# RF315Mhz.net
KiCad netlist of a schematic drawn in Altium Designer
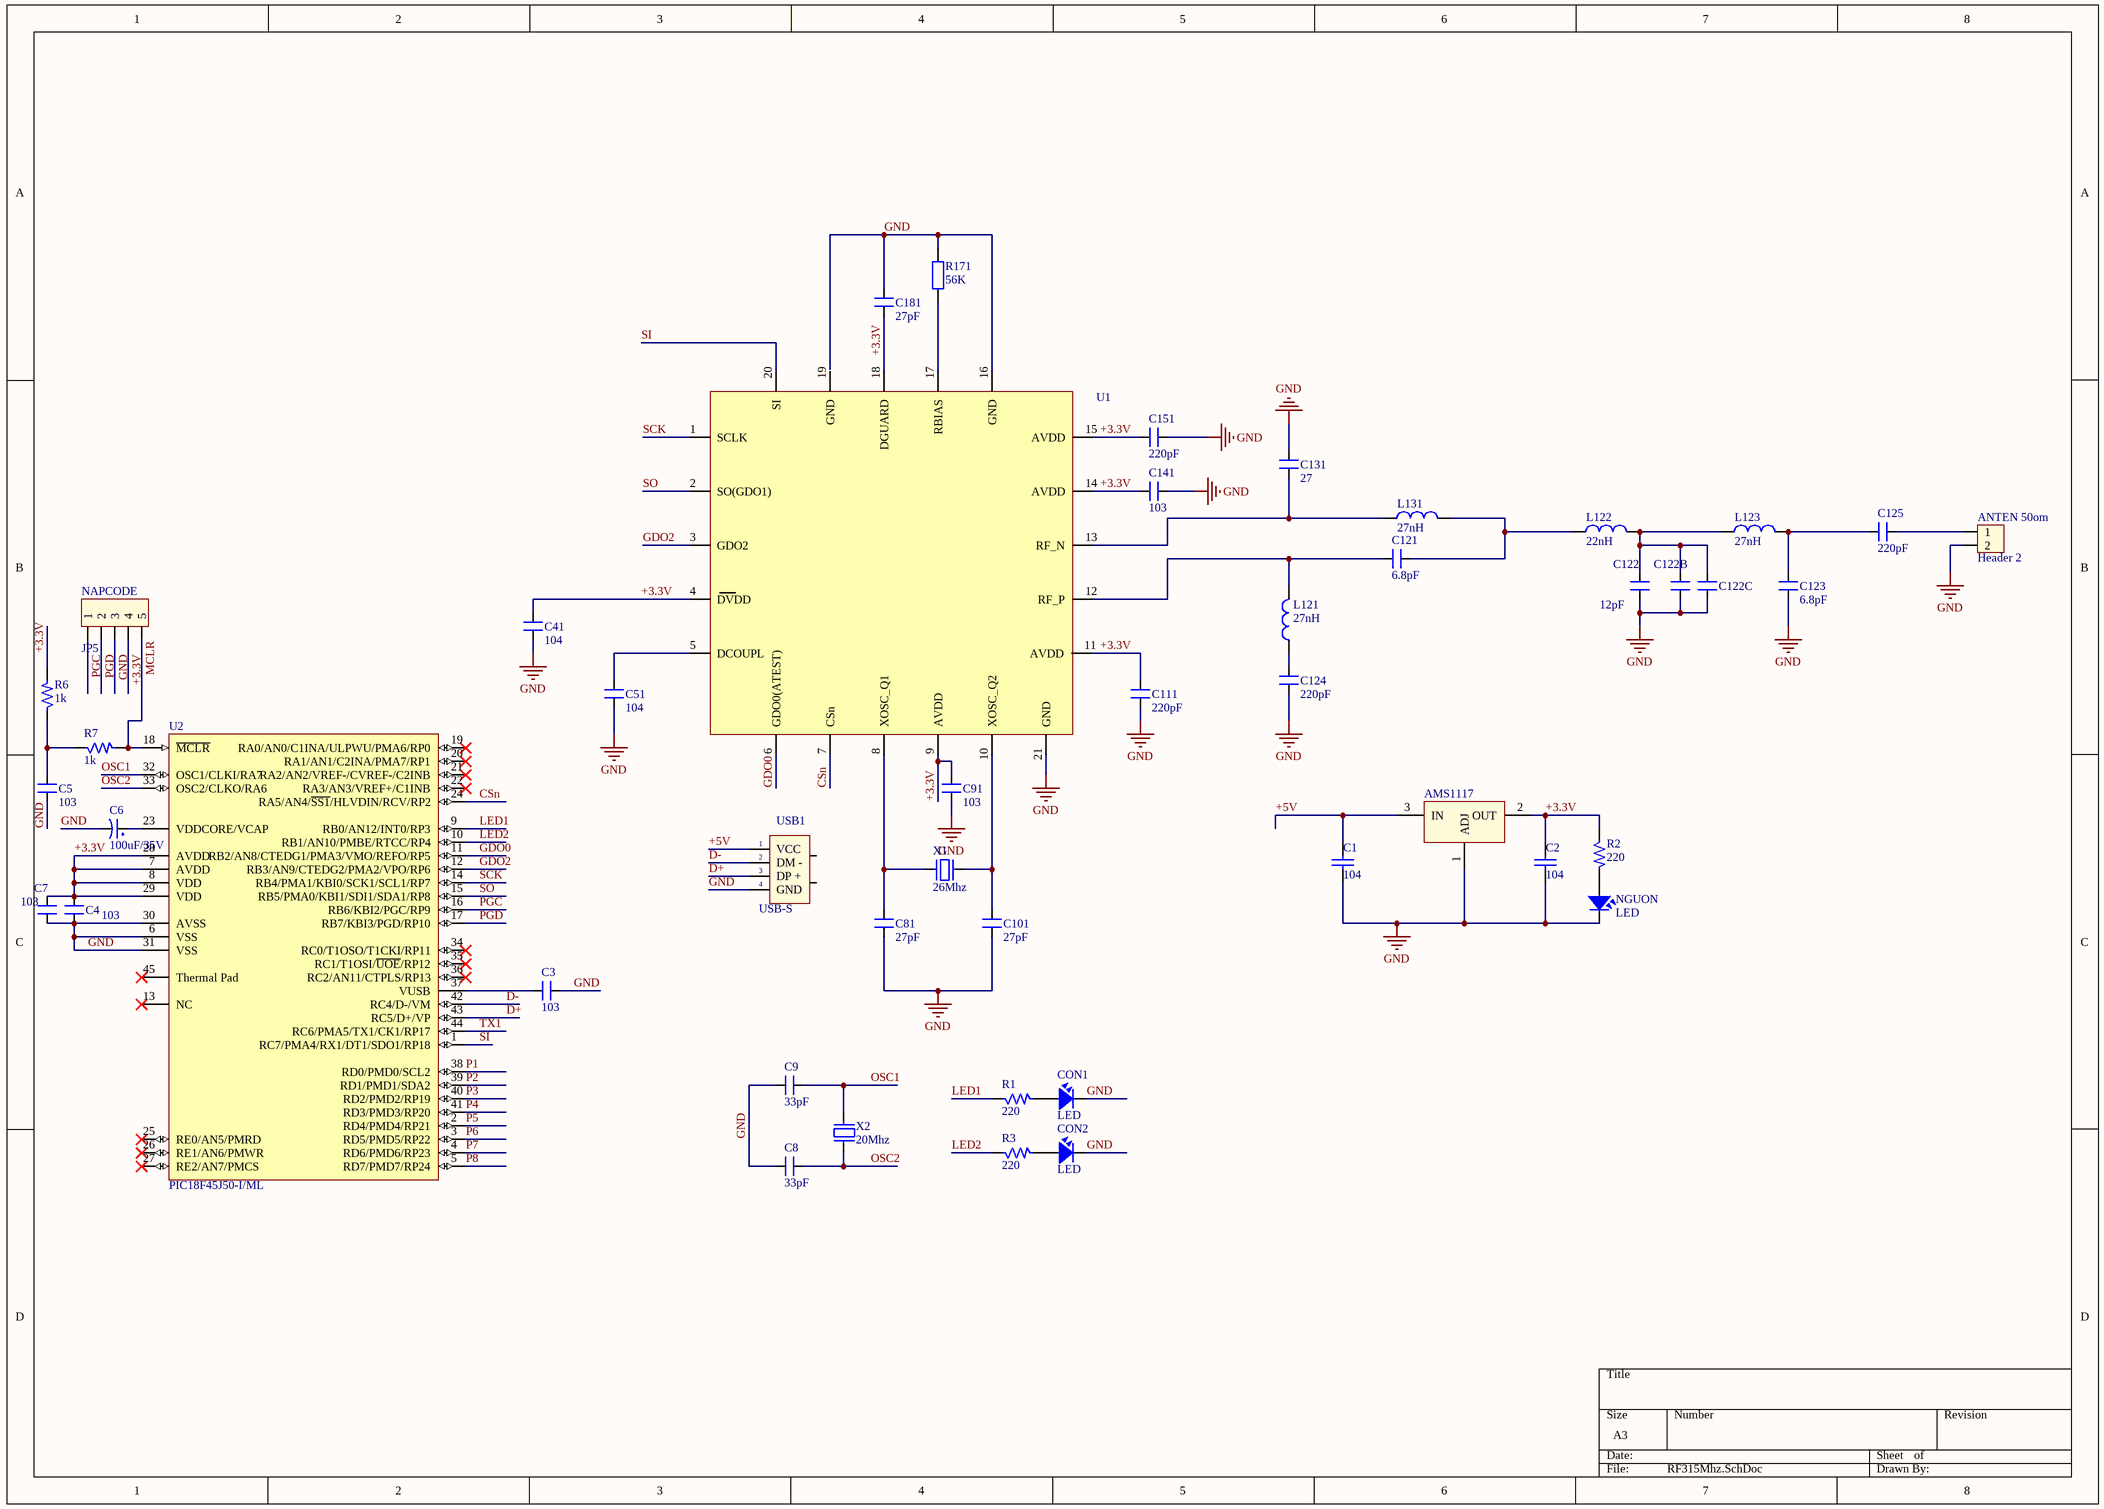
[diagram p0: RF315Mhz.SchDoc]

(export (version "E")
  (design (tool "Eeschema 10.0.6"))
  (components
    (comp (ref "AMS1117")
      (value "LM317")
      (footprint "SOT223-4N")
      (description "Adj Voltage +1.2 -> +37V")
      (libsource (lib "syhaunguyen") (part "LM317"))
    )
    (comp (ref "ANTEN 50om")
      (value "Header 2")
      (footprint "MCX5.08-H5")
      (description "Header 2 (Green)")
      (libsource (lib "syhaunguyen") (part "Hed2"))
    )
    (comp (ref "C1")
      (value "104")
      (footprint "0603ESDA")
      (description "Capacitor")
      (fields (field (name "PUBLISHER") "Altium Limited"))
      (libsource (lib "Miscellaneous Devices") (part "Cap"))
    )
    (comp (ref "C2")
      (value "104")
      (footprint "0603ESDA")
      (description "Capacitor")
      (fields (field (name "PUBLISHER") "Altium Limited"))
      (libsource (lib "Miscellaneous Devices") (part "Cap"))
    )
    (comp (ref "C3")
      (value "103")
      (footprint "SM-0805")
      (description "Cap SMD")
      (libsource (lib "syhaunguyen") (part "CM"))
    )
    (comp (ref "C4")
      (value "103")
      (footprint "SM-0805")
      (description "Cap SMD")
      (libsource (lib "syhaunguyen") (part "CM"))
    )
    (comp (ref "C5")
      (value "103")
      (footprint "SM-0805")
      (description "Cap SMD")
      (libsource (lib "syhaunguyen") (part "CM"))
    )
    (comp (ref "C6")
      (value "100uF/35V")
      (footprint "CP1/2.5_SM")
      (description "Cap 100uF/35V - 470uF/16V")
      (libsource (lib "syhaunguyen") (part "CP3"))
    )
    (comp (ref "C7")
      (value "103")
      (footprint "SM-0805")
      (description "Cap SMD")
      (libsource (lib "syhaunguyen") (part "CM"))
    )
    (comp (ref "C8")
      (value "33pF")
      (footprint "SM-0805")
      (description "Cremic For Xtal 1pF => 100pF")
      (libsource (lib "syhaunguyen") (part "CN0"))
    )
    (comp (ref "C9")
      (value "33pF")
      (footprint "SM-0805")
      (description "Cremic For Xtal 1pF => 100pF")
      (libsource (lib "syhaunguyen") (part "CN0"))
    )
    (comp (ref "C41")
      (value "104")
      (footprint "0603ESDA")
      (description "Cap SMD")
      (libsource (lib "syhaunguyen") (part "CM"))
    )
    (comp (ref "C51")
      (value "104")
      (footprint "0603ESDA")
      (description "Cap SMD")
      (libsource (lib "syhaunguyen") (part "CM"))
    )
    (comp (ref "C81")
      (value "27pF")
      (footprint "0603ESDA")
      (description "Cap SMD")
      (libsource (lib "syhaunguyen") (part "CM"))
    )
    (comp (ref "C91")
      (value "103")
      (footprint "0603ESDA")
      (description "Cap SMD")
      (libsource (lib "syhaunguyen") (part "CM"))
    )
    (comp (ref "C101")
      (value "27pF")
      (footprint "0603ESDA")
      (description "Cap SMD")
      (libsource (lib "syhaunguyen") (part "CM"))
    )
    (comp (ref "C111")
      (value "220pF")
      (footprint "0603ESDA")
      (description "Cap SMD")
      (libsource (lib "syhaunguyen") (part "CM"))
    )
    (comp (ref "C121")
      (value "6.8pF")
      (footprint "0603ESDA")
      (description "Cap SMD")
      (libsource (lib "syhaunguyen") (part "CM"))
    )
    (comp (ref "C122")
      (value "12pF")
      (footprint "0603ESDA")
      (description "Cap SMD")
      (libsource (lib "syhaunguyen") (part "CM"))
    )
    (comp (ref "C122B")
      (value "12pF")
      (footprint "0603ESDA")
      (description "Cap SMD")
      (libsource (lib "syhaunguyen") (part "CM"))
    )
    (comp (ref "C122C")
      (value "12pF")
      (footprint "0603ESDA")
      (description "Cap SMD")
      (libsource (lib "syhaunguyen") (part "CM"))
    )
    (comp (ref "C123")
      (value "6.8pF")
      (footprint "0603ESDA")
      (description "Cap SMD")
      (libsource (lib "syhaunguyen") (part "CM"))
    )
    (comp (ref "C124")
      (value "220pF")
      (footprint "0603ESDA")
      (description "Cap SMD")
      (libsource (lib "syhaunguyen") (part "CM"))
    )
    (comp (ref "C125")
      (value "220pF")
      (footprint "0603ESDA")
      (description "Cap SMD")
      (libsource (lib "syhaunguyen") (part "CM"))
    )
    (comp (ref "C131")
      (value "27")
      (footprint "0603ESDA")
      (description "Cap SMD")
      (libsource (lib "syhaunguyen") (part "CM"))
    )
    (comp (ref "C141")
      (value "103")
      (footprint "0603ESDA")
      (description "Cap SMD")
      (libsource (lib "syhaunguyen") (part "CM"))
    )
    (comp (ref "C151")
      (value "220pF")
      (footprint "0603ESDA")
      (description "Cap SMD")
      (libsource (lib "syhaunguyen") (part "CM"))
    )
    (comp (ref "C181")
      (value "27pF")
      (footprint "0603ESDA")
      (description "Cap SMD")
      (libsource (lib "syhaunguyen") (part "CM"))
    )
    (comp (ref "CON1")
      (value "LED")
      (footprint "LED3mm")
      (description "LED Single colour Green and Red")
      (libsource (lib "syhaunguyen") (part "LED"))
    )
    (comp (ref "CON2")
      (value "LED")
      (footprint "LED3mm")
      (description "LED Single colour Green and Red")
      (libsource (lib "syhaunguyen") (part "LED"))
    )
    (comp (ref "L121")
      (value "27nH")
      (footprint "SM-0805")
      (description "Inductor")
      (libsource (lib "syhaunguyen") (part "L1"))
    )
    (comp (ref "L122")
      (value "22nH")
      (footprint "SM-0805")
      (description "Inductor")
      (libsource (lib "syhaunguyen") (part "L1"))
    )
    (comp (ref "L123")
      (value "27nH")
      (footprint "SM-0805")
      (description "Inductor")
      (libsource (lib "syhaunguyen") (part "L1"))
    )
    (comp (ref "L131")
      (value "27nH")
      (footprint "SM-0805")
      (description "Inductor")
      (libsource (lib "syhaunguyen") (part "L1"))
    )
    (comp (ref "NAPCODE")
      (value "JP5")
      (footprint "CON5")
      (description "Connector 5")
      (libsource (lib "syhaunguyen") (part "Con5"))
    )
    (comp (ref "NGUON")
      (value "LED")
      (footprint "LED0805")
      (description "LED Single colour Green and Red")
      (libsource (lib "syhaunguyen") (part "LED"))
    )
    (comp (ref "R1")
      (value "220")
      (footprint "SM-0805")
      (description "Resistor 1/4W")
      (libsource (lib "syhaunguyen") (part "R"))
    )
    (comp (ref "R2")
      (value "220")
      (footprint "SM-0805")
      (description "Resistor 1/4W")
      (libsource (lib "syhaunguyen") (part "R"))
    )
    (comp (ref "R3")
      (value "220")
      (footprint "SM-0805")
      (description "Resistor 1/4W")
      (libsource (lib "syhaunguyen") (part "R"))
    )
    (comp (ref "R6")
      (value "1k")
      (footprint "SM-0805")
      (description "Resistor 1/4W")
      (libsource (lib "syhaunguyen") (part "R"))
    )
    (comp (ref "R7")
      (value "1k")
      (footprint "SM-0805")
      (description "Resistor 1/4W")
      (libsource (lib "syhaunguyen") (part "R"))
    )
    (comp (ref "R171")
      (value "56K")
      (footprint "SM-0805")
      (description "Resistor SMD")
      (libsource (lib "syhaunguyen") (part "RM"))
    )
    (comp (ref "U1")
      (value "CC1101")
      (footprint "QFN-20Pin")
      (description "Transceiver 315Mhz")
      (libsource (lib "syhaunguyen") (part "CC1101"))
    )
    (comp (ref "U2")
      (value "PIC18F45J50-I/ML")
      (footprint "PIC18F45J50SMD")
      (fields (field (name "PUBLISHER") "Altium Limited"))
      (libsource (lib "Microchip Microcontroller 8-Bit PIC18") (part "PIC18F45J50-I/ML"))
    )
    (comp (ref "USB1")
      (value "USB-S")
      (footprint "USB-A")
      (description "USB connector")
      (libsource (lib "syhaunguyen") (part "USB_S"))
    )
    (comp (ref "X1")
      (value "26Mhz")
      (footprint "XT2")
      (description "Crystal For all Crystal 2pin.")
      (libsource (lib "syhaunguyen") (part "XT2"))
    )
    (comp (ref "X2")
      (value "20Mhz")
      (footprint "XT2")
      (description "Crystal For all Crystal 2pin.")
      (libsource (lib "syhaunguyen") (part "XT2"))
    )
  )
  (nets
    (net (code "1") (name "/+3.3V") (class "Default")
      (node (ref "AMS1117") (pin "2") (pinfunction "OUT_2") (pintype "passive"))
      (node (ref "C111") (pin "2") (pinfunction "2_2") (pintype "passive"))
      (node (ref "C141") (pin "2") (pinfunction "2_2") (pintype "passive"))
      (node (ref "C151") (pin "1") (pinfunction "1_1") (pintype "passive"))
      (node (ref "C181") (pin "1") (pinfunction "1_1") (pintype "passive"))
      (node (ref "C2") (pin "2") (pinfunction "2_2") (pintype "passive"))
      (node (ref "C4") (pin "1") (pinfunction "1_1") (pintype "passive"))
      (node (ref "C41") (pin "2") (pinfunction "2_2") (pintype "passive"))
      (node (ref "C7") (pin "2") (pinfunction "2_2") (pintype "passive"))
      (node (ref "C91") (pin "2") (pinfunction "2_2") (pintype "passive"))
      (node (ref "NAPCODE") (pin "4") (pinfunction "4_4") (pintype "passive"))
      (node (ref "R2") (pin "1") (pinfunction "1_1") (pintype "passive"))
      (node (ref "R6") (pin "2") (pinfunction "2_2") (pintype "passive"))
      (node (ref "U1") (pin "11") (pinfunction "AVDD_11") (pintype "passive"))
      (node (ref "U1") (pin "14") (pinfunction "AVDD_14") (pintype "passive"))
      (node (ref "U1") (pin "15") (pinfunction "AVDD_15") (pintype "passive"))
      (node (ref "U1") (pin "18") (pinfunction "DGUARD_18") (pintype "passive"))
      (node (ref "U1") (pin "4") (pinfunction "DVDD_4") (pintype "passive"))
      (node (ref "U1") (pin "9") (pinfunction "AVDD_9") (pintype "passive"))
      (node (ref "U2") (pin "28") (pinfunction "AVDD_28") (pintype "power_in"))
      (node (ref "U2") (pin "29") (pinfunction "VDD_29") (pintype "power_in"))
      (node (ref "U2") (pin "7") (pinfunction "AVDD_7") (pintype "power_in"))
      (node (ref "U2") (pin "8") (pinfunction "VDD_8") (pintype "power_in"))
    )
    (net (code "2") (name "/+5V") (class "Default")
      (node (ref "AMS1117") (pin "3") (pinfunction "IN_3") (pintype "passive"))
      (node (ref "C1") (pin "2") (pinfunction "2_2") (pintype "passive"))
      (node (ref "USB1") (pin "1") (pinfunction "VCC_1") (pintype "passive"))
    )
    (net (code "3") (name "/CSn") (class "Default")
      (node (ref "U1") (pin "7") (pinfunction "CSn_7") (pintype "passive"))
      (node (ref "U2") (pin "24") (pinfunction "RA5/AN4/~{SS1}/HLVDIN/RCV/RP2_24") (pintype "bidirectional"))
    )
    (net (code "4") (name "/D+") (class "Default")
      (node (ref "U2") (pin "43") (pinfunction "RC5/D+/VP_43") (pintype "bidirectional"))
      (node (ref "USB1") (pin "3") (pinfunction "DP_+_3") (pintype "passive"))
    )
    (net (code "5") (name "/D-") (class "Default")
      (node (ref "U2") (pin "42") (pinfunction "RC4/D-/VM_42") (pintype "bidirectional"))
      (node (ref "USB1") (pin "2") (pinfunction "DM_-_2") (pintype "passive"))
    )
    (net (code "6") (name "/GDO0") (class "Default")
      (node (ref "U1") (pin "6") (pinfunction "GDO0(ATEST)_6") (pintype "passive"))
      (node (ref "U2") (pin "11") (pinfunction "RB2/AN8/CTEDG1/PMA3/VMO/REFO/RP5_11") (pintype "bidirectional"))
    )
    (net (code "7") (name "/GDO2") (class "Default")
      (node (ref "U1") (pin "3") (pinfunction "GDO2_3") (pintype "passive"))
      (node (ref "U2") (pin "12") (pinfunction "RB3/AN9/CTEDG2/PMA2/VPO/RP6_12") (pintype "bidirectional"))
    )
    (net (code "8") (name "/LED1") (class "Default")
      (node (ref "R1") (pin "1") (pinfunction "1_1") (pintype "passive"))
      (node (ref "U2") (pin "9") (pinfunction "RB0/AN12/INT0/RP3_9") (pintype "bidirectional"))
    )
    (net (code "9") (name "/LED2") (class "Default")
      (node (ref "R3") (pin "1") (pinfunction "1_1") (pintype "passive"))
      (node (ref "U2") (pin "10") (pinfunction "RB1/AN10/PMBE/RTCC/RP4_10") (pintype "bidirectional"))
    )
    (net (code "10") (name "/MCLR") (class "Default")
      (node (ref "NAPCODE") (pin "5") (pinfunction "5_5") (pintype "passive"))
      (node (ref "R7") (pin "2") (pinfunction "2_2") (pintype "passive"))
      (node (ref "U2") (pin "18") (pinfunction "~{MCLR}_18") (pintype "input"))
    )
    (net (code "11") (name "/OSC1") (class "Default")
      (node (ref "C9") (pin "2") (pinfunction "2_2") (pintype "passive"))
      (node (ref "U2") (pin "32") (pinfunction "OSC1/CLKI/RA7_32") (pintype "bidirectional"))
      (node (ref "X2") (pin "2") (pinfunction "2_2") (pintype "passive"))
    )
    (net (code "12") (name "/OSC2") (class "Default")
      (node (ref "C8") (pin "2") (pinfunction "2_2") (pintype "passive"))
      (node (ref "U2") (pin "33") (pinfunction "OSC2/CLKO/RA6_33") (pintype "bidirectional"))
      (node (ref "X2") (pin "1") (pinfunction "1_1") (pintype "passive"))
    )
    (net (code "13") (name "/P1") (class "Default")
      (node (ref "U2") (pin "38") (pinfunction "RD0/PMD0/SCL2_38") (pintype "bidirectional"))
    )
    (net (code "14") (name "/P2") (class "Default")
      (node (ref "U2") (pin "39") (pinfunction "RD1/PMD1/SDA2_39") (pintype "bidirectional"))
    )
    (net (code "15") (name "/P3") (class "Default")
      (node (ref "U2") (pin "40") (pinfunction "RD2/PMD2/RP19_40") (pintype "bidirectional"))
    )
    (net (code "16") (name "/P4") (class "Default")
      (node (ref "U2") (pin "41") (pinfunction "RD3/PMD3/RP20_41") (pintype "bidirectional"))
    )
    (net (code "17") (name "/P5") (class "Default")
      (node (ref "U2") (pin "2") (pinfunction "RD4/PMD4/RP21_2") (pintype "bidirectional"))
    )
    (net (code "18") (name "/P6") (class "Default")
      (node (ref "U2") (pin "3") (pinfunction "RD5/PMD5/RP22_3") (pintype "bidirectional"))
    )
    (net (code "19") (name "/P7") (class "Default")
      (node (ref "U2") (pin "4") (pinfunction "RD6/PMD6/RP23_4") (pintype "bidirectional"))
    )
    (net (code "20") (name "/P8") (class "Default")
      (node (ref "U2") (pin "5") (pinfunction "RD7/PMD7/RP24_5") (pintype "bidirectional"))
    )
    (net (code "21") (name "/PGC") (class "Default")
      (node (ref "NAPCODE") (pin "1") (pinfunction "1_1") (pintype "passive"))
      (node (ref "U2") (pin "16") (pinfunction "RB6/KBI2/PGC/RP9_16") (pintype "bidirectional"))
    )
    (net (code "22") (name "/PGD") (class "Default")
      (node (ref "NAPCODE") (pin "2") (pinfunction "2_2") (pintype "passive"))
      (node (ref "U2") (pin "17") (pinfunction "RB7/KBI3/PGD/RP10_17") (pintype "bidirectional"))
    )
    (net (code "23") (name "/SCK") (class "Default")
      (node (ref "U1") (pin "1") (pinfunction "SCLK_1") (pintype "passive"))
      (node (ref "U2") (pin "14") (pinfunction "RB4/PMA1/KBI0/SCK1/SCL1/RP7_14") (pintype "bidirectional"))
    )
    (net (code "24") (name "/SI") (class "Default")
      (node (ref "U1") (pin "20") (pinfunction "SI_20") (pintype "passive"))
      (node (ref "U2") (pin "1") (pinfunction "RC7/PMA4/RX1/DT1/SDO1/RP18_1") (pintype "bidirectional"))
    )
    (net (code "25") (name "/SO") (class "Default")
      (node (ref "U1") (pin "2") (pinfunction "SO(GDO1)_2") (pintype "passive"))
      (node (ref "U2") (pin "15") (pinfunction "RB5/PMA0/KBI1/SDI1/SDA1/RP8_15") (pintype "bidirectional"))
    )
    (net (code "26") (name "/TX1") (class "Default")
      (node (ref "U2") (pin "44") (pinfunction "RC6/PMA5/TX1/CK1/RP17_44") (pintype "bidirectional"))
    )
    (net (code "27") (name "GND") (class "Default")
      (node (ref "AMS1117") (pin "1") (pinfunction "ADJ_1") (pintype "passive"))
      (node (ref "ANTEN 50om") (pin "2") (pinfunction "2_2") (pintype "passive"))
      (node (ref "C1") (pin "1") (pinfunction "1_1") (pintype "passive"))
      (node (ref "C101") (pin "1") (pinfunction "1_1") (pintype "passive"))
      (node (ref "C111") (pin "1") (pinfunction "1_1") (pintype "passive"))
      (node (ref "C122") (pin "2") (pinfunction "2_2") (pintype "passive"))
      (node (ref "C122B") (pin "2") (pinfunction "2_2") (pintype "passive"))
      (node (ref "C122C") (pin "2") (pinfunction "2_2") (pintype "passive"))
      (node (ref "C123") (pin "2") (pinfunction "2_2") (pintype "passive"))
      (node (ref "C124") (pin "1") (pinfunction "1_1") (pintype "passive"))
      (node (ref "C131") (pin "2") (pinfunction "2_2") (pintype "passive"))
      (node (ref "C141") (pin "1") (pinfunction "1_1") (pintype "passive"))
      (node (ref "C151") (pin "2") (pinfunction "2_2") (pintype "passive"))
      (node (ref "C181") (pin "2") (pinfunction "2_2") (pintype "passive"))
      (node (ref "C2") (pin "1") (pinfunction "1_1") (pintype "passive"))
      (node (ref "C3") (pin "2") (pinfunction "2_2") (pintype "passive"))
      (node (ref "C4") (pin "2") (pinfunction "2_2") (pintype "passive"))
      (node (ref "C41") (pin "1") (pinfunction "1_1") (pintype "passive"))
      (node (ref "C5") (pin "1") (pinfunction "1_1") (pintype "passive"))
      (node (ref "C51") (pin "1") (pinfunction "1_1") (pintype "passive"))
      (node (ref "C6") (pin "2") (pinfunction "2_2") (pintype "passive"))
      (node (ref "C7") (pin "1") (pinfunction "1_1") (pintype "passive"))
      (node (ref "C8") (pin "1") (pinfunction "1_1") (pintype "passive"))
      (node (ref "C81") (pin "1") (pinfunction "1_1") (pintype "passive"))
      (node (ref "C9") (pin "1") (pinfunction "1_1") (pintype "passive"))
      (node (ref "C91") (pin "1") (pinfunction "1_1") (pintype "passive"))
      (node (ref "CON1") (pin "2") (pinfunction "2_2") (pintype "passive"))
      (node (ref "CON2") (pin "2") (pinfunction "2_2") (pintype "passive"))
      (node (ref "NAPCODE") (pin "3") (pinfunction "3_3") (pintype "passive"))
      (node (ref "NGUON") (pin "2") (pinfunction "2_2") (pintype "passive"))
      (node (ref "R171") (pin "2") (pinfunction "2_2") (pintype "passive"))
      (node (ref "U1") (pin "16") (pinfunction "GND_16") (pintype "passive"))
      (node (ref "U1") (pin "21") (pinfunction "GND_21") (pintype "passive"))
      (node (ref "U2") (pin "30") (pinfunction "AVSS_30") (pintype "power_in"))
      (node (ref "U2") (pin "31") (pinfunction "VSS_31") (pintype "power_in"))
      (node (ref "U2") (pin "6") (pinfunction "VSS_6") (pintype "power_in"))
      (node (ref "USB1") (pin "4") (pinfunction "GND_4") (pintype "passive"))
    )
    (net (code "28") (name "Net-(ANTEN 50om-Pad1)") (class "Default")
      (node (ref "ANTEN 50om") (pin "1") (pinfunction "1_1") (pintype "passive"))
      (node (ref "C125") (pin "2") (pinfunction "2_2") (pintype "passive"))
    )
    (net (code "29") (name "Net-(C5-Pad2)") (class "Default")
      (node (ref "C5") (pin "2") (pinfunction "2_2") (pintype "passive"))
      (node (ref "R6") (pin "1") (pinfunction "1_1") (pintype "passive"))
      (node (ref "R7") (pin "1") (pinfunction "1_1") (pintype "passive"))
    )
    (net (code "30") (name "Net-(C121-Pad1)") (class "Default")
      (node (ref "C121") (pin "1") (pinfunction "1_1") (pintype "passive"))
      (node (ref "L122") (pin "1") (pinfunction "1_1") (pintype "passive"))
      (node (ref "L131") (pin "2") (pinfunction "2_2") (pintype "passive"))
    )
    (net (code "31") (name "Net-(C122-Pad1)") (class "Default")
      (node (ref "C122") (pin "1") (pinfunction "1_1") (pintype "passive"))
      (node (ref "C122B") (pin "1") (pinfunction "1_1") (pintype "passive"))
      (node (ref "C122C") (pin "1") (pinfunction "1_1") (pintype "passive"))
      (node (ref "L122") (pin "2") (pinfunction "2_2") (pintype "passive"))
      (node (ref "L123") (pin "1") (pinfunction "1_1") (pintype "passive"))
    )
    (net (code "32") (name "Net-(C123-Pad1)") (class "Default")
      (node (ref "C123") (pin "1") (pinfunction "1_1") (pintype "passive"))
      (node (ref "C125") (pin "1") (pinfunction "1_1") (pintype "passive"))
      (node (ref "L123") (pin "2") (pinfunction "2_2") (pintype "passive"))
    )
    (net (code "33") (name "Net-(C124-Pad2)") (class "Default")
      (node (ref "C124") (pin "2") (pinfunction "2_2") (pintype "passive"))
      (node (ref "L121") (pin "1") (pinfunction "1_1") (pintype "passive"))
    )
    (net (code "34") (name "Net-(CON1-Pad1)") (class "Default")
      (node (ref "CON1") (pin "1") (pinfunction "1_1") (pintype "passive"))
      (node (ref "R1") (pin "2") (pinfunction "2_2") (pintype "passive"))
    )
    (net (code "35") (name "Net-(CON2-Pad1)") (class "Default")
      (node (ref "CON2") (pin "1") (pinfunction "1_1") (pintype "passive"))
      (node (ref "R3") (pin "2") (pinfunction "2_2") (pintype "passive"))
    )
    (net (code "36") (name "Net-(NGUON-Pad1)") (class "Default")
      (node (ref "NGUON") (pin "1") (pinfunction "1_1") (pintype "passive"))
      (node (ref "R2") (pin "2") (pinfunction "2_2") (pintype "passive"))
    )
    (net (code "37") (name "Net-(U1-DCOUPL)") (class "Default")
      (node (ref "C51") (pin "2") (pinfunction "2_2") (pintype "passive"))
      (node (ref "U1") (pin "5") (pinfunction "DCOUPL_5") (pintype "passive"))
    )
    (net (code "38") (name "Net-(U1-RBIAS)") (class "Default")
      (node (ref "R171") (pin "1") (pinfunction "1_1") (pintype "passive"))
      (node (ref "U1") (pin "17") (pinfunction "RBIAS_17") (pintype "passive"))
    )
    (net (code "39") (name "Net-(U1-RF_N)") (class "Default")
      (node (ref "C131") (pin "1") (pinfunction "1_1") (pintype "passive"))
      (node (ref "L131") (pin "1") (pinfunction "1_1") (pintype "passive"))
      (node (ref "U1") (pin "13") (pinfunction "RF_N_13") (pintype "passive"))
    )
    (net (code "40") (name "Net-(U1-RF_P)") (class "Default")
      (node (ref "C121") (pin "2") (pinfunction "2_2") (pintype "passive"))
      (node (ref "L121") (pin "2") (pinfunction "2_2") (pintype "passive"))
      (node (ref "U1") (pin "12") (pinfunction "RF_P_12") (pintype "passive"))
    )
    (net (code "41") (name "Net-(U1-XOSC_Q1)") (class "Default")
      (node (ref "C81") (pin "2") (pinfunction "2_2") (pintype "passive"))
      (node (ref "U1") (pin "8") (pinfunction "XOSC_Q1_8") (pintype "passive"))
      (node (ref "X1") (pin "1") (pinfunction "1_1") (pintype "passive"))
    )
    (net (code "42") (name "Net-(U1-XOSC_Q2)") (class "Default")
      (node (ref "C101") (pin "2") (pinfunction "2_2") (pintype "passive"))
      (node (ref "U1") (pin "10") (pinfunction "XOSC_Q2_10") (pintype "passive"))
      (node (ref "X1") (pin "2") (pinfunction "2_2") (pintype "passive"))
    )
    (net (code "43") (name "Net-(U2-VDDCORE{slash}VCAP)") (class "Default")
      (node (ref "C6") (pin "1") (pinfunction "1_1") (pintype "passive"))
      (node (ref "U2") (pin "23") (pinfunction "VDDCORE/VCAP_23") (pintype "power_in"))
    )
    (net (code "44") (name "Net-(U2-VUSB)") (class "Default")
      (node (ref "C3") (pin "1") (pinfunction "1_1") (pintype "passive"))
      (node (ref "U2") (pin "37") (pinfunction "VUSB_37") (pintype "power_in"))
    )
    (net (code "45") (name "unconnected-(U1-GND-Pad19)") (class "Default")
      (node (ref "U1") (pin "19") (pinfunction "GND_19") (pintype "passive"))
    )
    (net (code "46") (name "unconnected-(U2-NC-Pad13)") (class "Default")
      (node (ref "U2") (pin "13") (pinfunction "NC_13") (pintype "passive+no_connect"))
    )
    (net (code "47") (name "unconnected-(U2-RA0{slash}AN0{slash}C1INA{slash}ULPWU{slash}PMA6{slash}RP0-Pad19)") (class "Default")
      (node (ref "U2") (pin "19") (pinfunction "RA0/AN0/C1INA/ULPWU/PMA6/RP0_19") (pintype "bidirectional+no_connect"))
    )
    (net (code "48") (name "unconnected-(U2-RA1{slash}AN1{slash}C2INA{slash}PMA7{slash}RP1-Pad20)") (class "Default")
      (node (ref "U2") (pin "20") (pinfunction "RA1/AN1/C2INA/PMA7/RP1_20") (pintype "bidirectional+no_connect"))
    )
    (net (code "49") (name "unconnected-(U2-RA2{slash}AN2{slash}VREF-{slash}CVREF-{slash}C2INB-Pad21)") (class "Default")
      (node (ref "U2") (pin "21") (pinfunction "RA2/AN2/VREF-/CVREF-/C2INB_21") (pintype "bidirectional+no_connect"))
    )
    (net (code "50") (name "unconnected-(U2-RA3{slash}AN3{slash}VREF+{slash}C1INB-Pad22)") (class "Default")
      (node (ref "U2") (pin "22") (pinfunction "RA3/AN3/VREF+/C1INB_22") (pintype "bidirectional+no_connect"))
    )
    (net (code "51") (name "unconnected-(U2-RC0{slash}T1OSO{slash}T1CKI{slash}RP11-Pad34)") (class "Default")
      (node (ref "U2") (pin "34") (pinfunction "RC0/T1OSO/T1CKI/RP11_34") (pintype "bidirectional+no_connect"))
    )
    (net (code "52") (name "unconnected-(U2-RC1{slash}T1OSI{slash}~{UOE}{slash}RP12-Pad35)") (class "Default")
      (node (ref "U2") (pin "35") (pinfunction "RC1/T1OSI/~{UOE}/RP12_35") (pintype "bidirectional+no_connect"))
    )
    (net (code "53") (name "unconnected-(U2-RC2{slash}AN11{slash}CTPLS{slash}RP13-Pad36)") (class "Default")
      (node (ref "U2") (pin "36") (pinfunction "RC2/AN11/CTPLS/RP13_36") (pintype "bidirectional+no_connect"))
    )
    (net (code "54") (name "unconnected-(U2-RE0{slash}AN5{slash}PMRD-Pad25)") (class "Default")
      (node (ref "U2") (pin "25") (pinfunction "RE0/AN5/PMRD_25") (pintype "bidirectional+no_connect"))
    )
    (net (code "55") (name "unconnected-(U2-RE1{slash}AN6{slash}PMWR-Pad26)") (class "Default")
      (node (ref "U2") (pin "26") (pinfunction "RE1/AN6/PMWR_26") (pintype "bidirectional+no_connect"))
    )
    (net (code "56") (name "unconnected-(U2-RE2{slash}AN7{slash}PMCS-Pad27)") (class "Default")
      (node (ref "U2") (pin "27") (pinfunction "RE2/AN7/PMCS_27") (pintype "bidirectional+no_connect"))
    )
    (net (code "57") (name "unconnected-(U2-Thermal_Pad-Pad45)") (class "Default")
      (node (ref "U2") (pin "45") (pinfunction "Thermal_Pad_45") (pintype "power_in+no_connect"))
    )
    (net (code "58") (name "unconnected-(USB1-Pad5)") (class "Default")
      (node (ref "USB1") (pin "5") (pinfunction "5_5") (pintype "passive"))
    )
    (net (code "59") (name "unconnected-(USB1-Pad6)") (class "Default")
      (node (ref "USB1") (pin "6") (pinfunction "6_6") (pintype "passive"))
    )
  )
)
